# max7219-usb-angle.net
KiCad netlist of a schematic drawn in EAGLE
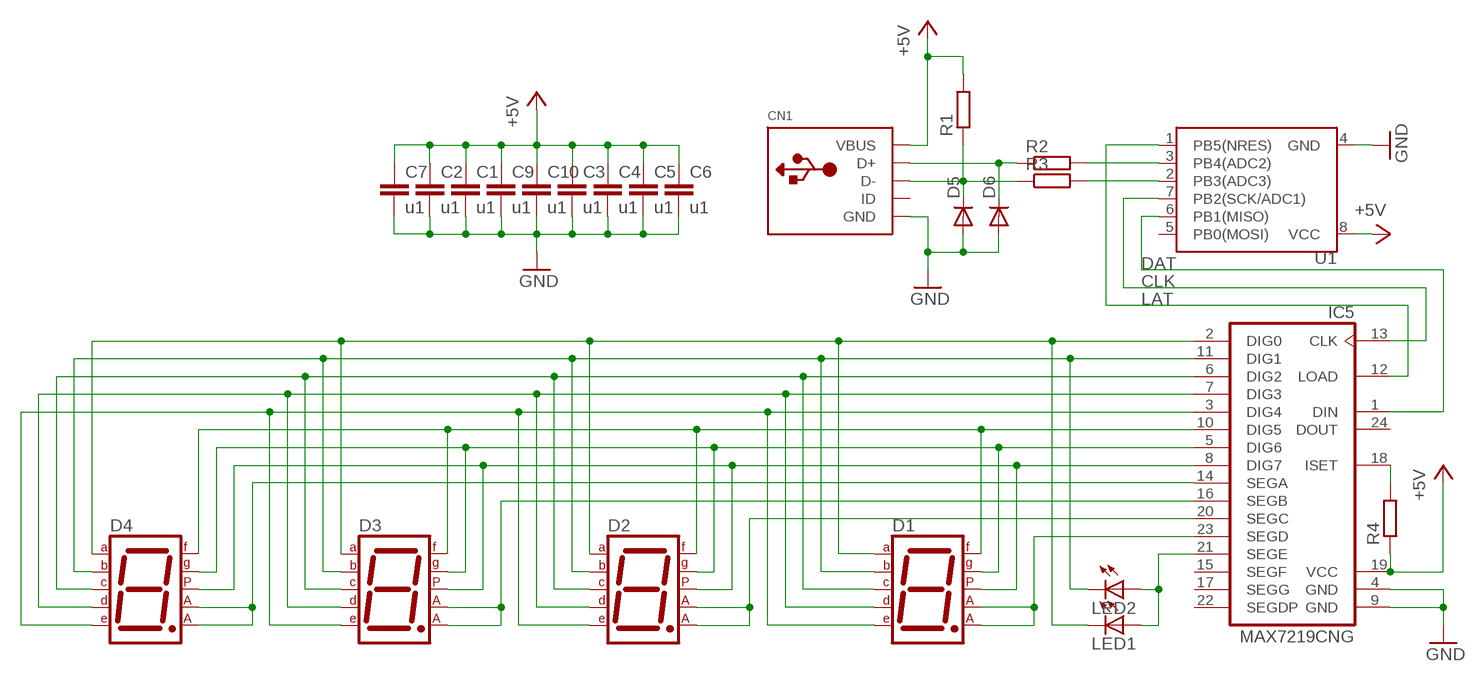
[diagram p0: schematic, sheet 1]

(export (version "E")
  (design (tool "Eeschema 10.0.6"))
  (components
    (comp (ref "C1")
      (value "u1")
      (footprint "eagle-import:C0805K")
      (libsource (lib "eagle-import") (part "C-EUC0805K"))
    )
    (comp (ref "C2")
      (value "u1")
      (footprint "eagle-import:C0805K")
      (libsource (lib "eagle-import") (part "C-EUC0805K"))
    )
    (comp (ref "C3")
      (value "u1")
      (footprint "eagle-import:C0805K")
      (libsource (lib "eagle-import") (part "C-EUC0805K"))
    )
    (comp (ref "C4")
      (value "u1")
      (footprint "eagle-import:C0805K")
      (libsource (lib "eagle-import") (part "C-EUC0805K"))
    )
    (comp (ref "C5")
      (value "u1")
      (footprint "eagle-import:C0805K")
      (libsource (lib "eagle-import") (part "C-EUC0805K"))
    )
    (comp (ref "C6")
      (value "u1")
      (footprint "eagle-import:C0805K")
      (libsource (lib "eagle-import") (part "C-EUC0805K"))
    )
    (comp (ref "C7")
      (value "u1")
      (footprint "eagle-import:C0805K")
      (libsource (lib "eagle-import") (part "C-EUC0805K"))
    )
    (comp (ref "C9")
      (value "u1")
      (footprint "eagle-import:C0805K")
      (libsource (lib "eagle-import") (part "C-EUC0805K"))
    )
    (comp (ref "C10")
      (value "u1")
      (footprint "eagle-import:C0805K")
      (libsource (lib "eagle-import") (part "C-EUC0805K"))
    )
    (comp (ref "CN1")
      (value "USBTHM")
      (footprint "eagle-import:USB-MINIB-THM")
      (libsource (lib "eagle-import") (part "USBTHM"))
    )
    (comp (ref "D1")
      (value "7SEG-CA")
      (footprint "eagle-import:7SEG-13")
      (libsource (lib "eagle-import") (part "7SEG-CA"))
    )
    (comp (ref "D2")
      (value "7SEG-CA")
      (footprint "eagle-import:7SEG-13")
      (libsource (lib "eagle-import") (part "7SEG-CA"))
    )
    (comp (ref "D3")
      (value "7SEG-CA")
      (footprint "eagle-import:7SEG-13")
      (libsource (lib "eagle-import") (part "7SEG-CA"))
    )
    (comp (ref "D4")
      (value "7SEG-CA")
      (footprint "eagle-import:7SEG-13")
      (libsource (lib "eagle-import") (part "7SEG-CA"))
    )
    (comp (ref "D5")
      (value "DIODE-MINIMELF")
      (footprint "eagle-import:MINIMELF")
      (libsource (lib "eagle-import") (part "DIODE-MINIMELF"))
    )
    (comp (ref "D6")
      (value "DIODE-MINIMELF")
      (footprint "eagle-import:MINIMELF")
      (libsource (lib "eagle-import") (part "DIODE-MINIMELF"))
    )
    (comp (ref "IC5")
      (value "MAX7219CNG")
      (footprint "eagle-import:DIL24-3")
      (fields (field (name "MF") "MAXIM"))
      (libsource (lib "eagle-import") (part "MAX7219CNG"))
    )
    (comp (ref "LED1")
      (value "LED3MM")
      (footprint "eagle-import:LED3MM")
      (libsource (lib "eagle-import") (part "LED3MM"))
    )
    (comp (ref "LED2")
      (value "LED3MM")
      (footprint "eagle-import:LED3MM")
      (libsource (lib "eagle-import") (part "LED3MM"))
    )
    (comp (ref "R1")
      (value "R-EU_M0805")
      (footprint "eagle-import:M0805")
      (libsource (lib "eagle-import") (part "R-EU_M0805"))
    )
    (comp (ref "R2")
      (value "R-EU_M0805")
      (footprint "eagle-import:M0805")
      (libsource (lib "eagle-import") (part "R-EU_M0805"))
    )
    (comp (ref "R3")
      (value "R-EU_M0805")
      (footprint "eagle-import:M0805")
      (libsource (lib "eagle-import") (part "R-EU_M0805"))
    )
    (comp (ref "R4")
      (value "R-EU_R0805")
      (footprint "eagle-import:R0805")
      (libsource (lib "eagle-import") (part "R-EU_R0805"))
    )
    (comp (ref "U1")
      (value "ATTINY45ATTINYX5-20-DIP-GAP")
      (footprint "eagle-import:DIL08")
      (libsource (lib "eagle-import") (part "ATTINY45ATTINYX5-20-DIP-GAP"))
    )
  )
  (nets
    (net (code "1") (name "+5V") (class "Default")
      (node (ref "C1") (pin "1") (pinfunction "1_1") (pintype "passive"))
      (node (ref "C10") (pin "1") (pinfunction "1_1") (pintype "passive"))
      (node (ref "C2") (pin "1") (pinfunction "1_1") (pintype "passive"))
      (node (ref "C3") (pin "1") (pinfunction "1_1") (pintype "passive"))
      (node (ref "C4") (pin "1") (pinfunction "1_1") (pintype "passive"))
      (node (ref "C5") (pin "1") (pinfunction "1_1") (pintype "passive"))
      (node (ref "C6") (pin "1") (pinfunction "1_1") (pintype "passive"))
      (node (ref "C7") (pin "1") (pinfunction "1_1") (pintype "passive"))
      (node (ref "C9") (pin "1") (pinfunction "1_1") (pintype "passive"))
      (node (ref "CN1") (pin "VBUS") (pinfunction "VBUS_VBUS") (pintype "power_in"))
      (node (ref "IC5") (pin "19") (pinfunction "VCC_19") (pintype "power_in"))
      (node (ref "R1") (pin "2") (pinfunction "2_2") (pintype "passive"))
      (node (ref "R4") (pin "1") (pinfunction "1_1") (pintype "passive"))
      (node (ref "U1") (pin "8") (pinfunction "VCC_8") (pintype "bidirectional"))
    )
    (net (code "2") (name "/CLK") (class "Default")
      (node (ref "IC5") (pin "13") (pinfunction "CLK_13") (pintype "input"))
      (node (ref "U1") (pin "7") (pinfunction "PB2(SCK/ADC1)_7") (pintype "bidirectional"))
    )
    (net (code "3") (name "/DAT") (class "Default")
      (node (ref "IC5") (pin "1") (pinfunction "DIN_1") (pintype "input"))
      (node (ref "U1") (pin "6") (pinfunction "PB1(MISO)_6") (pintype "bidirectional"))
    )
    (net (code "4") (name "/LAT") (class "Default")
      (node (ref "IC5") (pin "12") (pinfunction "LOAD_12") (pintype "input"))
      (node (ref "U1") (pin "1") (pinfunction "PB5(NRES)_1") (pintype "bidirectional"))
    )
    (net (code "5") (name "GND") (class "Default")
      (node (ref "C1") (pin "2") (pinfunction "2_2") (pintype "passive"))
      (node (ref "C10") (pin "2") (pinfunction "2_2") (pintype "passive"))
      (node (ref "C2") (pin "2") (pinfunction "2_2") (pintype "passive"))
      (node (ref "C3") (pin "2") (pinfunction "2_2") (pintype "passive"))
      (node (ref "C4") (pin "2") (pinfunction "2_2") (pintype "passive"))
      (node (ref "C5") (pin "2") (pinfunction "2_2") (pintype "passive"))
      (node (ref "C6") (pin "2") (pinfunction "2_2") (pintype "passive"))
      (node (ref "C7") (pin "2") (pinfunction "2_2") (pintype "passive"))
      (node (ref "C9") (pin "2") (pinfunction "2_2") (pintype "passive"))
      (node (ref "CN1") (pin "GND") (pinfunction "GND_GND") (pintype "power_in"))
      (node (ref "D5") (pin "A") (pinfunction "A_A") (pintype "passive"))
      (node (ref "D6") (pin "A") (pinfunction "A_A") (pintype "passive"))
      (node (ref "IC5") (pin "4") (pinfunction "GND_4") (pintype "power_in"))
      (node (ref "IC5") (pin "9") (pinfunction "GND_9") (pintype "power_in"))
      (node (ref "U1") (pin "4") (pinfunction "GND_4") (pintype "bidirectional"))
    )
    (net (code "6") (name "Net-(CN1-PadD+)") (class "Default")
      (node (ref "CN1") (pin "D+") (pinfunction "D+_D+") (pintype "bidirectional"))
      (node (ref "D6") (pin "C") (pinfunction "C_C") (pintype "passive"))
      (node (ref "R2") (pin "1") (pinfunction "1_1") (pintype "passive"))
    )
    (net (code "7") (name "Net-(CN1-PadD-)") (class "Default")
      (node (ref "CN1") (pin "D-") (pinfunction "D-_D-") (pintype "bidirectional"))
      (node (ref "D5") (pin "C") (pinfunction "C_C") (pintype "passive"))
      (node (ref "R1") (pin "1") (pinfunction "1_1") (pintype "passive"))
      (node (ref "R3") (pin "1") (pinfunction "1_1") (pintype "passive"))
    )
    (net (code "8") (name "Net-(D1-A)") (class "Default")
      (node (ref "D1") (pin "7") (pinfunction "A_7") (pintype "passive"))
      (node (ref "D2") (pin "7") (pinfunction "A_7") (pintype "passive"))
      (node (ref "D3") (pin "7") (pinfunction "A_7") (pintype "passive"))
      (node (ref "D4") (pin "7") (pinfunction "A_7") (pintype "passive"))
      (node (ref "IC5") (pin "2") (pinfunction "DIG0_2") (pintype "output"))
      (node (ref "LED1") (pin "K") (pinfunction "C_K") (pintype "passive"))
    )
    (net (code "9") (name "Net-(D1-B)") (class "Default")
      (node (ref "D1") (pin "6") (pinfunction "B_6") (pintype "passive"))
      (node (ref "D2") (pin "6") (pinfunction "B_6") (pintype "passive"))
      (node (ref "D3") (pin "6") (pinfunction "B_6") (pintype "passive"))
      (node (ref "D4") (pin "6") (pinfunction "B_6") (pintype "passive"))
      (node (ref "IC5") (pin "11") (pinfunction "DIG1_11") (pintype "output"))
      (node (ref "LED2") (pin "K") (pinfunction "C_K") (pintype "passive"))
    )
    (net (code "10") (name "Net-(D1-C)") (class "Default")
      (node (ref "D1") (pin "4") (pinfunction "C_4") (pintype "passive"))
      (node (ref "D2") (pin "4") (pinfunction "C_4") (pintype "passive"))
      (node (ref "D3") (pin "4") (pinfunction "C_4") (pintype "passive"))
      (node (ref "D4") (pin "4") (pinfunction "C_4") (pintype "passive"))
      (node (ref "IC5") (pin "6") (pinfunction "DIG2_6") (pintype "output"))
    )
    (net (code "11") (name "Net-(D1-CA1)") (class "Default")
      (node (ref "D1") (pin "3") (pinfunction "CA1_3") (pintype "passive"))
      (node (ref "D1") (pin "8") (pinfunction "CA2_8") (pintype "passive"))
      (node (ref "IC5") (pin "23") (pinfunction "SEGD_23") (pintype "output"))
    )
    (net (code "12") (name "Net-(D1-D)") (class "Default")
      (node (ref "D1") (pin "2") (pinfunction "D_2") (pintype "passive"))
      (node (ref "D2") (pin "2") (pinfunction "D_2") (pintype "passive"))
      (node (ref "D3") (pin "2") (pinfunction "D_2") (pintype "passive"))
      (node (ref "D4") (pin "2") (pinfunction "D_2") (pintype "passive"))
      (node (ref "IC5") (pin "7") (pinfunction "DIG3_7") (pintype "output"))
    )
    (net (code "13") (name "Net-(D1-DP)") (class "Default")
      (node (ref "D1") (pin "5") (pinfunction "DP_5") (pintype "passive"))
      (node (ref "D2") (pin "5") (pinfunction "DP_5") (pintype "passive"))
      (node (ref "D3") (pin "5") (pinfunction "DP_5") (pintype "passive"))
      (node (ref "D4") (pin "5") (pinfunction "DP_5") (pintype "passive"))
      (node (ref "IC5") (pin "8") (pinfunction "DIG7_8") (pintype "output"))
    )
    (net (code "14") (name "Net-(D1-E)") (class "Default")
      (node (ref "D1") (pin "1") (pinfunction "E_1") (pintype "passive"))
      (node (ref "D2") (pin "1") (pinfunction "E_1") (pintype "passive"))
      (node (ref "D3") (pin "1") (pinfunction "E_1") (pintype "passive"))
      (node (ref "D4") (pin "1") (pinfunction "E_1") (pintype "passive"))
      (node (ref "IC5") (pin "3") (pinfunction "DIG4_3") (pintype "output"))
    )
    (net (code "15") (name "Net-(D1-F)") (class "Default")
      (node (ref "D1") (pin "9") (pinfunction "F_9") (pintype "passive"))
      (node (ref "D2") (pin "9") (pinfunction "F_9") (pintype "passive"))
      (node (ref "D3") (pin "9") (pinfunction "F_9") (pintype "passive"))
      (node (ref "D4") (pin "9") (pinfunction "F_9") (pintype "passive"))
      (node (ref "IC5") (pin "10") (pinfunction "DIG5_10") (pintype "output"))
    )
    (net (code "16") (name "Net-(D1-G)") (class "Default")
      (node (ref "D1") (pin "10") (pinfunction "G_10") (pintype "passive"))
      (node (ref "D2") (pin "10") (pinfunction "G_10") (pintype "passive"))
      (node (ref "D3") (pin "10") (pinfunction "G_10") (pintype "passive"))
      (node (ref "D4") (pin "10") (pinfunction "G_10") (pintype "passive"))
      (node (ref "IC5") (pin "5") (pinfunction "DIG6_5") (pintype "output"))
    )
    (net (code "17") (name "Net-(D2-CA1)") (class "Default")
      (node (ref "D2") (pin "3") (pinfunction "CA1_3") (pintype "passive"))
      (node (ref "D2") (pin "8") (pinfunction "CA2_8") (pintype "passive"))
      (node (ref "IC5") (pin "20") (pinfunction "SEGC_20") (pintype "output"))
    )
    (net (code "18") (name "Net-(D3-CA1)") (class "Default")
      (node (ref "D3") (pin "3") (pinfunction "CA1_3") (pintype "passive"))
      (node (ref "D3") (pin "8") (pinfunction "CA2_8") (pintype "passive"))
      (node (ref "IC5") (pin "16") (pinfunction "SEGB_16") (pintype "output"))
    )
    (net (code "19") (name "Net-(D4-CA1)") (class "Default")
      (node (ref "D4") (pin "3") (pinfunction "CA1_3") (pintype "passive"))
      (node (ref "D4") (pin "8") (pinfunction "CA2_8") (pintype "passive"))
      (node (ref "IC5") (pin "14") (pinfunction "SEGA_14") (pintype "output"))
    )
    (net (code "20") (name "Net-(IC5-ISET)") (class "Default")
      (node (ref "IC5") (pin "18") (pinfunction "ISET_18") (pintype "input"))
      (node (ref "R4") (pin "2") (pinfunction "2_2") (pintype "passive"))
    )
    (net (code "21") (name "Net-(IC5-SEGE)") (class "Default")
      (node (ref "IC5") (pin "21") (pinfunction "SEGE_21") (pintype "output"))
      (node (ref "LED1") (pin "A") (pinfunction "A_A") (pintype "passive"))
      (node (ref "LED2") (pin "A") (pinfunction "A_A") (pintype "passive"))
    )
    (net (code "22") (name "Net-(U1-PB3(ADC3))") (class "Default")
      (node (ref "R3") (pin "2") (pinfunction "2_2") (pintype "passive"))
      (node (ref "U1") (pin "2") (pinfunction "PB3(ADC3)_2") (pintype "bidirectional"))
    )
    (net (code "23") (name "Net-(U1-PB4(ADC2))") (class "Default")
      (node (ref "R2") (pin "2") (pinfunction "2_2") (pintype "passive"))
      (node (ref "U1") (pin "3") (pinfunction "PB4(ADC2)_3") (pintype "bidirectional"))
    )
    (net (code "24") (name "unconnected-(CN1-PadID)") (class "Default")
      (node (ref "CN1") (pin "ID") (pinfunction "ID_ID") (pintype "bidirectional"))
    )
    (net (code "25") (name "unconnected-(IC5-DOUT-Pad24)") (class "Default")
      (node (ref "IC5") (pin "24") (pinfunction "DOUT_24") (pintype "output"))
    )
    (net (code "26") (name "unconnected-(IC5-SEGDP-Pad22)") (class "Default")
      (node (ref "IC5") (pin "22") (pinfunction "SEGDP_22") (pintype "output"))
    )
    (net (code "27") (name "unconnected-(IC5-SEGF-Pad15)") (class "Default")
      (node (ref "IC5") (pin "15") (pinfunction "SEGF_15") (pintype "output"))
    )
    (net (code "28") (name "unconnected-(IC5-SEGG-Pad17)") (class "Default")
      (node (ref "IC5") (pin "17") (pinfunction "SEGG_17") (pintype "output"))
    )
    (net (code "29") (name "unconnected-(U1-PB0(MOSI)-Pad5)") (class "Default")
      (node (ref "U1") (pin "5") (pinfunction "PB0(MOSI)_5") (pintype "bidirectional"))
    )
  )
)
